# EEGAmp_SMT_MountHole_Castellated.net
KiCad netlist of a schematic drawn in EAGLE
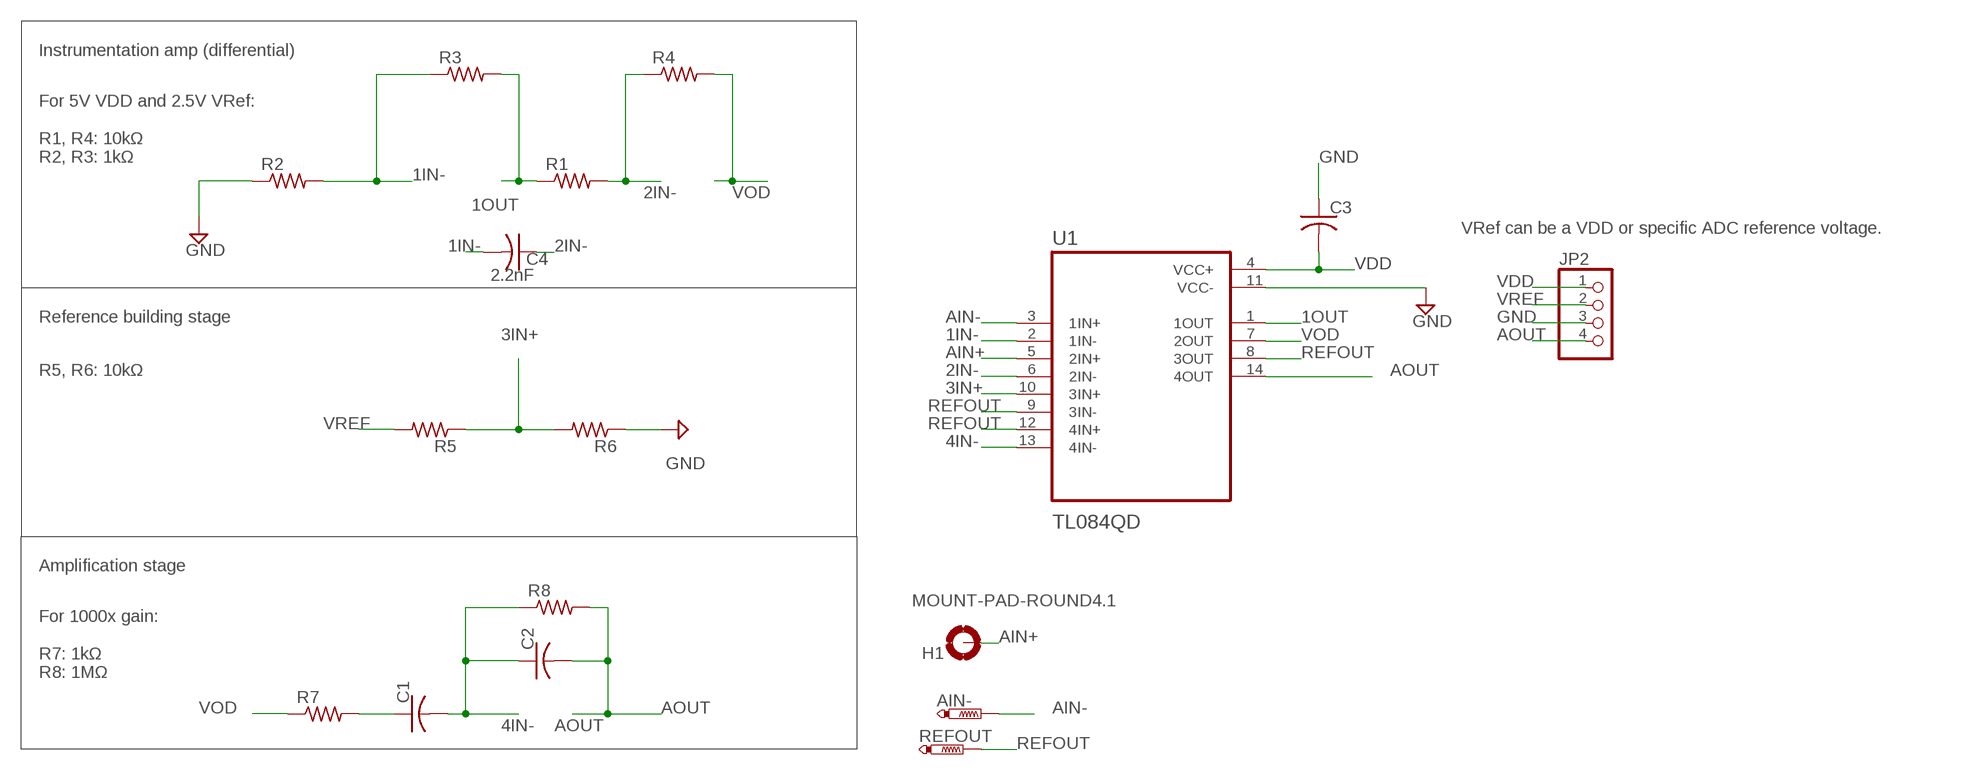
[diagram p0: schematic, sheet 1]

(export (version "E")
  (design (tool "Eeschema 10.0.6"))
  (components
    (comp (ref "AIN-")
      (value "PTR1PAD1-17")
      (footprint "eagle-import:P1-17")
      (libsource (lib "eagle-import") (part "PTR1PAD1-17"))
    )
    (comp (ref "C1")
      (value "C-USC0402")
      (footprint "eagle-import:C0402")
      (libsource (lib "eagle-import") (part "C-USC0402"))
    )
    (comp (ref "C2")
      (value "C-USC0402")
      (footprint "eagle-import:C0402")
      (libsource (lib "eagle-import") (part "C-USC0402"))
    )
    (comp (ref "C3")
      (value "C-USC0402")
      (footprint "eagle-import:C0402")
      (libsource (lib "eagle-import") (part "C-USC0402"))
    )
    (comp (ref "C4")
      (value "2.2nF")
      (footprint "eagle-import:C0402")
      (libsource (lib "eagle-import") (part "C-USC0402"))
    )
    (comp (ref "H1")
      (value "MOUNT-PAD-ROUND4.1")
      (footprint "eagle-import:4,1-PAD")
      (libsource (lib "eagle-import") (part "MOUNT-PAD-ROUND4.1"))
    )
    (comp (ref "JP2")
      (value "PINHD-1X4")
      (footprint "eagle-import:1X04")
      (libsource (lib "eagle-import") (part "PINHD-1X4"))
    )
    (comp (ref "R1")
      (value "R-US_R0402")
      (footprint "eagle-import:R0402")
      (libsource (lib "eagle-import") (part "R-US_R0402"))
    )
    (comp (ref "R2")
      (value "R-US_R0402")
      (footprint "eagle-import:R0402")
      (libsource (lib "eagle-import") (part "R-US_R0402"))
    )
    (comp (ref "R3")
      (value "R-US_R0402")
      (footprint "eagle-import:R0402")
      (libsource (lib "eagle-import") (part "R-US_R0402"))
    )
    (comp (ref "R4")
      (value "R-US_R0402")
      (footprint "eagle-import:R0402")
      (libsource (lib "eagle-import") (part "R-US_R0402"))
    )
    (comp (ref "R5")
      (value "R-US_R0402")
      (footprint "eagle-import:R0402")
      (libsource (lib "eagle-import") (part "R-US_R0402"))
    )
    (comp (ref "R6")
      (value "R-US_R0402")
      (footprint "eagle-import:R0402")
      (libsource (lib "eagle-import") (part "R-US_R0402"))
    )
    (comp (ref "R7")
      (value "R-US_R0402")
      (footprint "eagle-import:R0402")
      (libsource (lib "eagle-import") (part "R-US_R0402"))
    )
    (comp (ref "R8")
      (value "R-US_R0402")
      (footprint "eagle-import:R0402")
      (libsource (lib "eagle-import") (part "R-US_R0402"))
    )
    (comp (ref "REFOUT")
      (value "PTR1PAD1-17")
      (footprint "eagle-import:P1-17")
      (libsource (lib "eagle-import") (part "PTR1PAD1-17"))
    )
    (comp (ref "U1")
      (value "TL084QD")
      (footprint "eagle-import:SOIC127P600X175-14N")
      (fields (field (name "MF") "Texas Instruments"))
      (libsource (lib "eagle-import") (part "TL084QD"))
    )
  )
  (nets
    (net (code "1") (name "/1IN-") (class "Default")
      (node (ref "C4") (pin "2") (pinfunction "2_2") (pintype "passive"))
      (node (ref "R2") (pin "2") (pinfunction "2_2") (pintype "passive"))
      (node (ref "R3") (pin "1") (pinfunction "1_1") (pintype "passive"))
      (node (ref "U1") (pin "2") (pinfunction "1IN-_2") (pintype "input"))
    )
    (net (code "2") (name "/1OUT") (class "Default")
      (node (ref "R1") (pin "1") (pinfunction "1_1") (pintype "passive"))
      (node (ref "R3") (pin "2") (pinfunction "2_2") (pintype "passive"))
      (node (ref "U1") (pin "1") (pinfunction "1OUT_1") (pintype "output"))
    )
    (net (code "3") (name "/2IN-") (class "Default")
      (node (ref "C4") (pin "1") (pinfunction "1_1") (pintype "passive"))
      (node (ref "R1") (pin "2") (pinfunction "2_2") (pintype "passive"))
      (node (ref "R4") (pin "1") (pinfunction "1_1") (pintype "passive"))
      (node (ref "U1") (pin "6") (pinfunction "2IN-_6") (pintype "input"))
    )
    (net (code "4") (name "/3IN+") (class "Default")
      (node (ref "R5") (pin "1") (pinfunction "1_1") (pintype "passive"))
      (node (ref "R6") (pin "2") (pinfunction "2_2") (pintype "passive"))
      (node (ref "U1") (pin "10") (pinfunction "3IN+_10") (pintype "input"))
    )
    (net (code "5") (name "/4IN-") (class "Default")
      (node (ref "C1") (pin "2") (pinfunction "2_2") (pintype "passive"))
      (node (ref "C2") (pin "1") (pinfunction "1_1") (pintype "passive"))
      (node (ref "R8") (pin "1") (pinfunction "1_1") (pintype "passive"))
      (node (ref "U1") (pin "13") (pinfunction "4IN-_13") (pintype "input"))
    )
    (net (code "6") (name "/AIN+") (class "Default")
      (node (ref "H1") (pin "B4,1") (pinfunction "MOUNT_B4,1") (pintype "passive"))
      (node (ref "U1") (pin "5") (pinfunction "2IN+_5") (pintype "input"))
    )
    (net (code "7") (name "/AIN-") (class "Default")
      (node (ref "AIN-") (pin "TP") (pinfunction "TP_TP") (pintype "input"))
      (node (ref "U1") (pin "3") (pinfunction "1IN+_3") (pintype "input"))
    )
    (net (code "8") (name "/AOUT") (class "Default")
      (node (ref "C2") (pin "2") (pinfunction "2_2") (pintype "passive"))
      (node (ref "JP2") (pin "4") (pinfunction "4_4") (pintype "passive"))
      (node (ref "R8") (pin "2") (pinfunction "2_2") (pintype "passive"))
      (node (ref "U1") (pin "14") (pinfunction "4OUT_14") (pintype "output"))
    )
    (net (code "9") (name "/REFOUT") (class "Default")
      (node (ref "REFOUT") (pin "TP") (pinfunction "TP_TP") (pintype "input"))
      (node (ref "U1") (pin "12") (pinfunction "4IN+_12") (pintype "input"))
      (node (ref "U1") (pin "8") (pinfunction "3OUT_8") (pintype "output"))
      (node (ref "U1") (pin "9") (pinfunction "3IN-_9") (pintype "input"))
    )
    (net (code "10") (name "/VDD") (class "Default")
      (node (ref "C3") (pin "2") (pinfunction "2_2") (pintype "passive"))
      (node (ref "JP2") (pin "1") (pinfunction "1_1") (pintype "passive"))
      (node (ref "U1") (pin "4") (pinfunction "VCC+_4") (pintype "power_in"))
    )
    (net (code "11") (name "/VOD") (class "Default")
      (node (ref "R4") (pin "2") (pinfunction "2_2") (pintype "passive"))
      (node (ref "R7") (pin "1") (pinfunction "1_1") (pintype "passive"))
      (node (ref "U1") (pin "7") (pinfunction "2OUT_7") (pintype "output"))
    )
    (net (code "12") (name "/VREF") (class "Default")
      (node (ref "JP2") (pin "2") (pinfunction "2_2") (pintype "passive"))
      (node (ref "R5") (pin "2") (pinfunction "2_2") (pintype "passive"))
    )
    (net (code "13") (name "GND") (class "Default")
      (node (ref "C3") (pin "1") (pinfunction "1_1") (pintype "passive"))
      (node (ref "JP2") (pin "3") (pinfunction "3_3") (pintype "passive"))
      (node (ref "R2") (pin "1") (pinfunction "1_1") (pintype "passive"))
      (node (ref "R6") (pin "1") (pinfunction "1_1") (pintype "passive"))
      (node (ref "U1") (pin "11") (pinfunction "VCC-_11") (pintype "power_in"))
    )
    (net (code "14") (name "Net-(C1-Pad1)") (class "Default")
      (node (ref "C1") (pin "1") (pinfunction "1_1") (pintype "passive"))
      (node (ref "R7") (pin "2") (pinfunction "2_2") (pintype "passive"))
    )
  )
)
